# Buzzer.net
KiCad netlist of a schematic drawn in Altium Designer
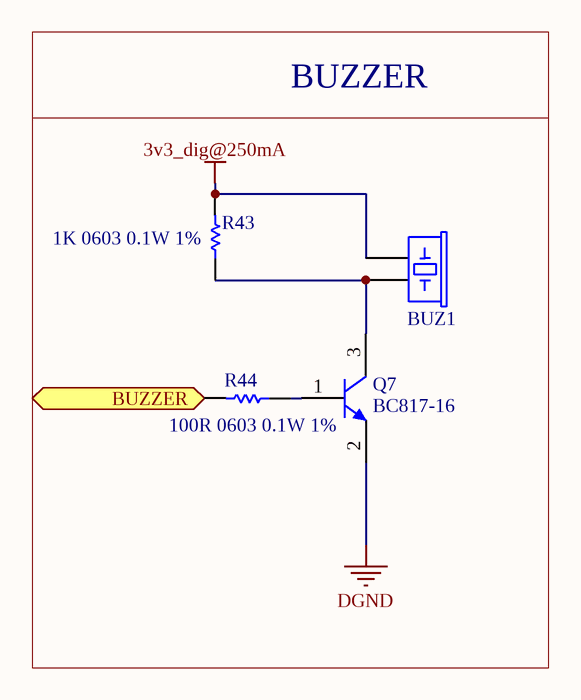
[diagram p0: Buzzer.SchDoc]

(export (version "E")
  (design (tool "Eeschema 10.0.6"))
  (components
    (comp (ref "BUZ1")
      (value "CUI CMT-1285C-035")
      (footprint "BUZZER-12MM-NS")
      (description "Audio Buzzer Magnetic 3Vo-p 5Vo-p 70mA 3.5Vo-p 85dB Through Hole Pin Tray")
      (fields (field (name "MANUFACTURER PART NUMBER") "CMT-1285C-035"))
      (libsource (lib "CommunityVault") (part "CMP-581a9557be5887dd-1"))
    )
    (comp (ref "Q7")
      (value "BC817-16")
      (footprint "PCB-856332-1")
      (description "TRANS NPN 45V 500mA SMD SOT23-3")
      (libsource (lib "CommunityVault") (part "CMP-856332-3"))
    )
    (comp (ref "R43")
      (value "1K 0603 0.1W 1%")
      (footprint "RESC1609X55X30ML10T20")
      (fields (field (name "MANUFACTURER PART NUMBER") "CR0603-FX-1001ELF"))
      (libsource (lib "CommunityVault") (part "CMP-a61f6f36030f79d8-4"))
    )
    (comp (ref "R44")
      (value "100R 0603 0.1W 1%")
      (footprint "RESC1609X55X30ML10T20")
      (fields (field (name "MANUFACTURER PART NUMBER") "CR0603-FX-1001ELF"))
      (libsource (lib "CommunityVault") (part "CMP-a61f6f36030f79d8-4"))
    )
  )
  (nets
    (net (code "1") (name "/BUZZER") (class "Default")
      (node (ref "R44") (pin "2") (pinfunction "2_2") (pintype "passive"))
    )
    (net (code "2") (name "3v3_dig@250mA") (class "Default")
      (node (ref "BUZ1") (pin "1") (pinfunction "+_1") (pintype "passive"))
      (node (ref "R43") (pin "2") (pinfunction "2_2") (pintype "passive"))
    )
    (net (code "3") (name "DGND") (class "Default")
      (node (ref "Q7") (pin "2") (pinfunction "E_2") (pintype "passive"))
    )
    (net (code "4") (name "Net-(BUZ1--)") (class "Default")
      (node (ref "BUZ1") (pin "2") (pinfunction "-_2") (pintype "passive"))
      (node (ref "Q7") (pin "3") (pinfunction "C_3") (pintype "passive"))
      (node (ref "R43") (pin "1") (pinfunction "1_1") (pintype "passive"))
    )
    (net (code "5") (name "Net-(Q7-B)") (class "Default")
      (node (ref "Q7") (pin "1") (pinfunction "B_1") (pintype "passive"))
      (node (ref "R44") (pin "1") (pinfunction "1_1") (pintype "passive"))
    )
  )
)
